# main.net
KiCad netlist of a schematic drawn in EAGLE
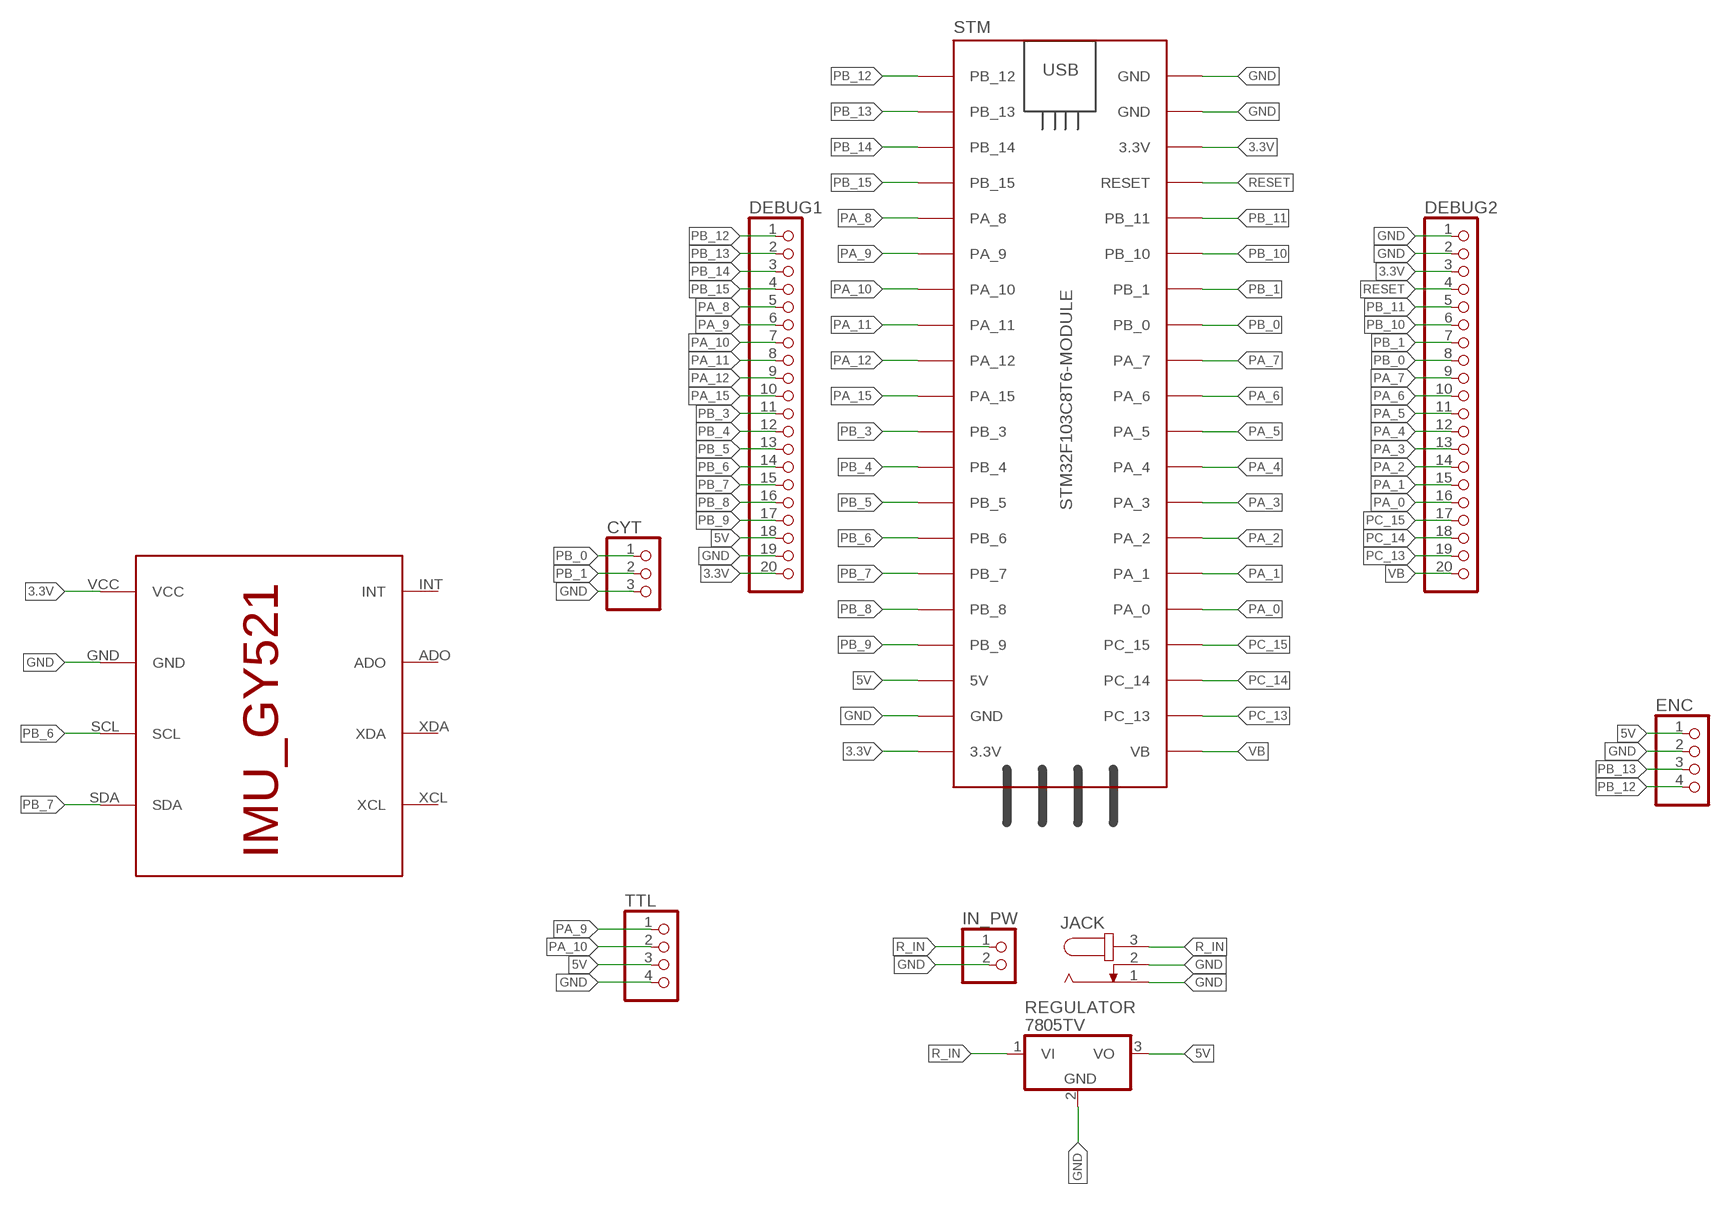
[diagram p0: schematic, sheet 1]

(export (version "E")
  (design (tool "Eeschema 10.0.6"))
  (components
    (comp (ref "CYT")
      (value "PINHD-1X3")
      (footprint "eagle-import:1X03")
      (libsource (lib "eagle-import") (part "PINHD-1X3"))
    )
    (comp (ref "DEBUG1")
      (value "PINHD-1X20")
      (footprint "eagle-import:1X20")
      (libsource (lib "eagle-import") (part "PINHD-1X20"))
    )
    (comp (ref "DEBUG2")
      (value "PINHD-1X20")
      (footprint "eagle-import:1X20")
      (libsource (lib "eagle-import") (part "PINHD-1X20"))
    )
    (comp (ref "ENC")
      (value "PINHD-1X4")
      (footprint "eagle-import:1X04")
      (libsource (lib "eagle-import") (part "PINHD-1X4"))
    )
    (comp (ref "IMU")
      (value "IMU_ROBOCON_GY521")
      (footprint "eagle-import:IMU_GY521")
      (libsource (lib "eagle-import") (part "IMU_ROBOCON_GY521"))
    )
    (comp (ref "IN_PW")
      (value "PINHD-2_DATA")
      (footprint "eagle-import:1X02_DATA")
      (libsource (lib "eagle-import") (part "PINHD-2_DATA"))
    )
    (comp (ref "JACK")
      (value "JACK-PLUG0")
      (footprint "eagle-import:SPC4077")
      (libsource (lib "eagle-import") (part "JACK-PLUG0"))
    )
    (comp (ref "REGULATOR")
      (value "7805TV")
      (footprint "eagle-import:TO220V")
      (libsource (lib "eagle-import") (part "78TV05"))
    )
    (comp (ref "STM")
      (value "STM32F103C8T6-MODULE")
      (footprint "eagle-import:STM32F103C8T6-MODULE")
      (libsource (lib "eagle-import") (part "STM32F103C8T6-MODULE"))
    )
    (comp (ref "TTL")
      (value "PINHD-1X4")
      (footprint "eagle-import:1X04")
      (libsource (lib "eagle-import") (part "PINHD-1X4"))
    )
  )
  (nets
    (net (code "1") (name "3.3V") (class "Default")
      (node (ref "DEBUG1") (pin "20") (pinfunction "20_20") (pintype "passive"))
      (node (ref "DEBUG2") (pin "3") (pinfunction "3_3") (pintype "passive"))
      (node (ref "IMU") (pin "VCC") (pinfunction "VCC_VCC") (pintype "bidirectional"))
      (node (ref "STM") (pin "3.3V_1") (pinfunction "3.3V_3.3V_1") (pintype "bidirectional"))
      (node (ref "STM") (pin "3.3V_2") (pinfunction "3.3V_3.3V_2") (pintype "bidirectional"))
    )
    (net (code "2") (name "5V") (class "Default")
      (node (ref "DEBUG1") (pin "18") (pinfunction "18_18") (pintype "passive"))
      (node (ref "ENC") (pin "1") (pinfunction "1_1") (pintype "passive"))
      (node (ref "REGULATOR") (pin "3") (pinfunction "VO_3") (pintype "passive"))
      (node (ref "STM") (pin "5V") (pinfunction "5V_5V") (pintype "bidirectional"))
      (node (ref "TTL") (pin "3") (pinfunction "3_3") (pintype "passive"))
    )
    (net (code "3") (name "GND") (class "Default")
      (node (ref "CYT") (pin "3") (pinfunction "3_3") (pintype "passive"))
      (node (ref "DEBUG1") (pin "19") (pinfunction "19_19") (pintype "passive"))
      (node (ref "DEBUG2") (pin "1") (pinfunction "1_1") (pintype "passive"))
      (node (ref "DEBUG2") (pin "2") (pinfunction "2_2") (pintype "passive"))
      (node (ref "ENC") (pin "2") (pinfunction "2_2") (pintype "passive"))
      (node (ref "IMU") (pin "GND") (pinfunction "GND_GND") (pintype "bidirectional"))
      (node (ref "IN_PW") (pin "2") (pinfunction "2_2") (pintype "passive"))
      (node (ref "JACK") (pin "1") (pinfunction "1_1") (pintype "passive"))
      (node (ref "JACK") (pin "2") (pinfunction "2_2") (pintype "passive"))
      (node (ref "REGULATOR") (pin "2") (pinfunction "GND_2") (pintype "passive"))
      (node (ref "STM") (pin "GND_1") (pinfunction "GND_GND_1") (pintype "bidirectional"))
      (node (ref "STM") (pin "GND_2") (pinfunction "GND_GND_2") (pintype "bidirectional"))
      (node (ref "STM") (pin "GND_3") (pinfunction "GND_GND_3") (pintype "power_in"))
      (node (ref "TTL") (pin "4") (pinfunction "4_4") (pintype "passive"))
    )
    (net (code "4") (name "PA_0") (class "Default")
      (node (ref "DEBUG2") (pin "16") (pinfunction "16_16") (pintype "passive"))
      (node (ref "STM") (pin "PA_0") (pinfunction "PA_0_PA_0") (pintype "bidirectional"))
    )
    (net (code "5") (name "PA_1") (class "Default")
      (node (ref "DEBUG2") (pin "15") (pinfunction "15_15") (pintype "passive"))
      (node (ref "STM") (pin "PA_1") (pinfunction "PA_1_PA_1") (pintype "bidirectional"))
    )
    (net (code "6") (name "PA_2") (class "Default")
      (node (ref "DEBUG2") (pin "14") (pinfunction "14_14") (pintype "passive"))
      (node (ref "STM") (pin "PA_2") (pinfunction "PA_2_PA_2") (pintype "bidirectional"))
    )
    (net (code "7") (name "PA_3") (class "Default")
      (node (ref "DEBUG2") (pin "13") (pinfunction "13_13") (pintype "passive"))
      (node (ref "STM") (pin "PA_3") (pinfunction "PA_3_PA_3") (pintype "bidirectional"))
    )
    (net (code "8") (name "PA_4") (class "Default")
      (node (ref "DEBUG2") (pin "12") (pinfunction "12_12") (pintype "passive"))
      (node (ref "STM") (pin "PA_4") (pinfunction "PA_4_PA_4") (pintype "bidirectional"))
    )
    (net (code "9") (name "PA_5") (class "Default")
      (node (ref "DEBUG2") (pin "11") (pinfunction "11_11") (pintype "passive"))
      (node (ref "STM") (pin "PA_5") (pinfunction "PA_5_PA_5") (pintype "bidirectional"))
    )
    (net (code "10") (name "PA_6") (class "Default")
      (node (ref "DEBUG2") (pin "10") (pinfunction "10_10") (pintype "passive"))
      (node (ref "STM") (pin "PA_6") (pinfunction "PA_6_PA_6") (pintype "bidirectional"))
    )
    (net (code "11") (name "PA_7") (class "Default")
      (node (ref "DEBUG2") (pin "9") (pinfunction "9_9") (pintype "passive"))
      (node (ref "STM") (pin "PA_7") (pinfunction "PA_7_PA_7") (pintype "bidirectional"))
    )
    (net (code "12") (name "PA_8") (class "Default")
      (node (ref "DEBUG1") (pin "5") (pinfunction "5_5") (pintype "passive"))
      (node (ref "STM") (pin "PA_8") (pinfunction "PA_8_PA_8") (pintype "bidirectional"))
    )
    (net (code "13") (name "PA_9") (class "Default")
      (node (ref "DEBUG1") (pin "6") (pinfunction "6_6") (pintype "passive"))
      (node (ref "STM") (pin "PA_9") (pinfunction "PA_9_PA_9") (pintype "bidirectional"))
      (node (ref "TTL") (pin "1") (pinfunction "1_1") (pintype "passive"))
    )
    (net (code "14") (name "PA_10") (class "Default")
      (node (ref "DEBUG1") (pin "7") (pinfunction "7_7") (pintype "passive"))
      (node (ref "STM") (pin "PA_10") (pinfunction "PA_10_PA_10") (pintype "bidirectional"))
      (node (ref "TTL") (pin "2") (pinfunction "2_2") (pintype "passive"))
    )
    (net (code "15") (name "PA_11") (class "Default")
      (node (ref "DEBUG1") (pin "8") (pinfunction "8_8") (pintype "passive"))
      (node (ref "STM") (pin "PA_11") (pinfunction "PA_11_PA_11") (pintype "bidirectional"))
    )
    (net (code "16") (name "PA_12") (class "Default")
      (node (ref "DEBUG1") (pin "9") (pinfunction "9_9") (pintype "passive"))
      (node (ref "STM") (pin "PA_12") (pinfunction "PA_12_PA_12") (pintype "bidirectional"))
    )
    (net (code "17") (name "PA_15") (class "Default")
      (node (ref "DEBUG1") (pin "10") (pinfunction "10_10") (pintype "passive"))
      (node (ref "STM") (pin "PA_15") (pinfunction "PA_15_PA_15") (pintype "bidirectional"))
    )
    (net (code "18") (name "PB_0") (class "Default")
      (node (ref "CYT") (pin "1") (pinfunction "1_1") (pintype "passive"))
      (node (ref "DEBUG2") (pin "8") (pinfunction "8_8") (pintype "passive"))
      (node (ref "STM") (pin "PB_0") (pinfunction "PB_0_PB_0") (pintype "bidirectional"))
    )
    (net (code "19") (name "PB_1") (class "Default")
      (node (ref "CYT") (pin "2") (pinfunction "2_2") (pintype "passive"))
      (node (ref "DEBUG2") (pin "7") (pinfunction "7_7") (pintype "passive"))
      (node (ref "STM") (pin "PB_1") (pinfunction "PB_1_PB_1") (pintype "bidirectional"))
    )
    (net (code "20") (name "PB_3") (class "Default")
      (node (ref "DEBUG1") (pin "11") (pinfunction "11_11") (pintype "passive"))
      (node (ref "STM") (pin "PB_3") (pinfunction "PB_3_PB_3") (pintype "bidirectional"))
    )
    (net (code "21") (name "PB_4") (class "Default")
      (node (ref "DEBUG1") (pin "12") (pinfunction "12_12") (pintype "passive"))
      (node (ref "STM") (pin "PB_4") (pinfunction "PB_4_PB_4") (pintype "bidirectional"))
    )
    (net (code "22") (name "PB_5") (class "Default")
      (node (ref "DEBUG1") (pin "13") (pinfunction "13_13") (pintype "passive"))
      (node (ref "STM") (pin "PB_5") (pinfunction "PB_5_PB_5") (pintype "bidirectional"))
    )
    (net (code "23") (name "PB_6") (class "Default")
      (node (ref "DEBUG1") (pin "14") (pinfunction "14_14") (pintype "passive"))
      (node (ref "IMU") (pin "SCL") (pinfunction "SCL_SCL") (pintype "bidirectional"))
      (node (ref "STM") (pin "PB_6") (pinfunction "PB_6_PB_6") (pintype "bidirectional"))
    )
    (net (code "24") (name "PB_7") (class "Default")
      (node (ref "DEBUG1") (pin "15") (pinfunction "15_15") (pintype "passive"))
      (node (ref "IMU") (pin "SDA") (pinfunction "SDA_SDA") (pintype "bidirectional"))
      (node (ref "STM") (pin "PB_7") (pinfunction "PB_7_PB_7") (pintype "bidirectional"))
    )
    (net (code "25") (name "PB_8") (class "Default")
      (node (ref "DEBUG1") (pin "16") (pinfunction "16_16") (pintype "passive"))
      (node (ref "STM") (pin "PB_8") (pinfunction "PB_8_PB_8") (pintype "bidirectional"))
    )
    (net (code "26") (name "PB_9") (class "Default")
      (node (ref "DEBUG1") (pin "17") (pinfunction "17_17") (pintype "passive"))
      (node (ref "STM") (pin "PB_9") (pinfunction "PB_9_PB_9") (pintype "bidirectional"))
    )
    (net (code "27") (name "PB_10") (class "Default")
      (node (ref "DEBUG2") (pin "6") (pinfunction "6_6") (pintype "passive"))
      (node (ref "STM") (pin "PB_10") (pinfunction "PB_10_PB_10") (pintype "bidirectional"))
    )
    (net (code "28") (name "PB_11") (class "Default")
      (node (ref "DEBUG2") (pin "5") (pinfunction "5_5") (pintype "passive"))
      (node (ref "STM") (pin "PB_11") (pinfunction "PB_11_PB_11") (pintype "bidirectional"))
    )
    (net (code "29") (name "PB_12") (class "Default")
      (node (ref "DEBUG1") (pin "1") (pinfunction "1_1") (pintype "passive"))
      (node (ref "ENC") (pin "4") (pinfunction "4_4") (pintype "passive"))
      (node (ref "STM") (pin "PB_12") (pinfunction "PB_12_PB_12") (pintype "bidirectional"))
    )
    (net (code "30") (name "PB_13") (class "Default")
      (node (ref "DEBUG1") (pin "2") (pinfunction "2_2") (pintype "passive"))
      (node (ref "ENC") (pin "3") (pinfunction "3_3") (pintype "passive"))
      (node (ref "STM") (pin "PB_13") (pinfunction "PB_13_PB_13") (pintype "bidirectional"))
    )
    (net (code "31") (name "PB_14") (class "Default")
      (node (ref "DEBUG1") (pin "3") (pinfunction "3_3") (pintype "passive"))
      (node (ref "STM") (pin "PB_14") (pinfunction "PB_14_PB_14") (pintype "bidirectional"))
    )
    (net (code "32") (name "PB_15") (class "Default")
      (node (ref "DEBUG1") (pin "4") (pinfunction "4_4") (pintype "passive"))
      (node (ref "STM") (pin "PB_15") (pinfunction "PB_15_PB_15") (pintype "bidirectional"))
    )
    (net (code "33") (name "PC_13") (class "Default")
      (node (ref "DEBUG2") (pin "19") (pinfunction "19_19") (pintype "passive"))
      (node (ref "STM") (pin "PC_13") (pinfunction "PC_13_PC_13") (pintype "bidirectional"))
    )
    (net (code "34") (name "PC_14") (class "Default")
      (node (ref "DEBUG2") (pin "18") (pinfunction "18_18") (pintype "passive"))
      (node (ref "STM") (pin "PC_14") (pinfunction "PC_14_PC_14") (pintype "bidirectional"))
    )
    (net (code "35") (name "PC_15") (class "Default")
      (node (ref "DEBUG2") (pin "17") (pinfunction "17_17") (pintype "passive"))
      (node (ref "STM") (pin "PC_15") (pinfunction "PC_15_PC_15") (pintype "bidirectional"))
    )
    (net (code "36") (name "RESET") (class "Default")
      (node (ref "DEBUG2") (pin "4") (pinfunction "4_4") (pintype "passive"))
      (node (ref "STM") (pin "RESET") (pinfunction "RESET_RESET") (pintype "bidirectional"))
    )
    (net (code "37") (name "R_IN") (class "Default")
      (node (ref "IN_PW") (pin "1") (pinfunction "1_1") (pintype "passive"))
      (node (ref "JACK") (pin "3") (pinfunction "3_3") (pintype "passive"))
      (node (ref "REGULATOR") (pin "1") (pinfunction "VI_1") (pintype "input"))
    )
    (net (code "38") (name "VB") (class "Default")
      (node (ref "DEBUG2") (pin "20") (pinfunction "20_20") (pintype "passive"))
      (node (ref "STM") (pin "VB") (pinfunction "VB_VB") (pintype "bidirectional"))
    )
    (net (code "39") (name "unconnected-(IMU-PadADO)") (class "Default")
      (node (ref "IMU") (pin "ADO") (pinfunction "ADO_ADO") (pintype "bidirectional"))
    )
    (net (code "40") (name "unconnected-(IMU-PadINT)") (class "Default")
      (node (ref "IMU") (pin "INT") (pinfunction "INT_INT") (pintype "bidirectional"))
    )
    (net (code "41") (name "unconnected-(IMU-PadXCL)") (class "Default")
      (node (ref "IMU") (pin "XCL") (pinfunction "XCL_XCL") (pintype "bidirectional"))
    )
    (net (code "42") (name "unconnected-(IMU-PadXDA)") (class "Default")
      (node (ref "IMU") (pin "XDA") (pinfunction "XDA_XDA") (pintype "bidirectional"))
    )
  )
)
